# big7segment.net
KiCad netlist of a schematic drawn in EAGLE
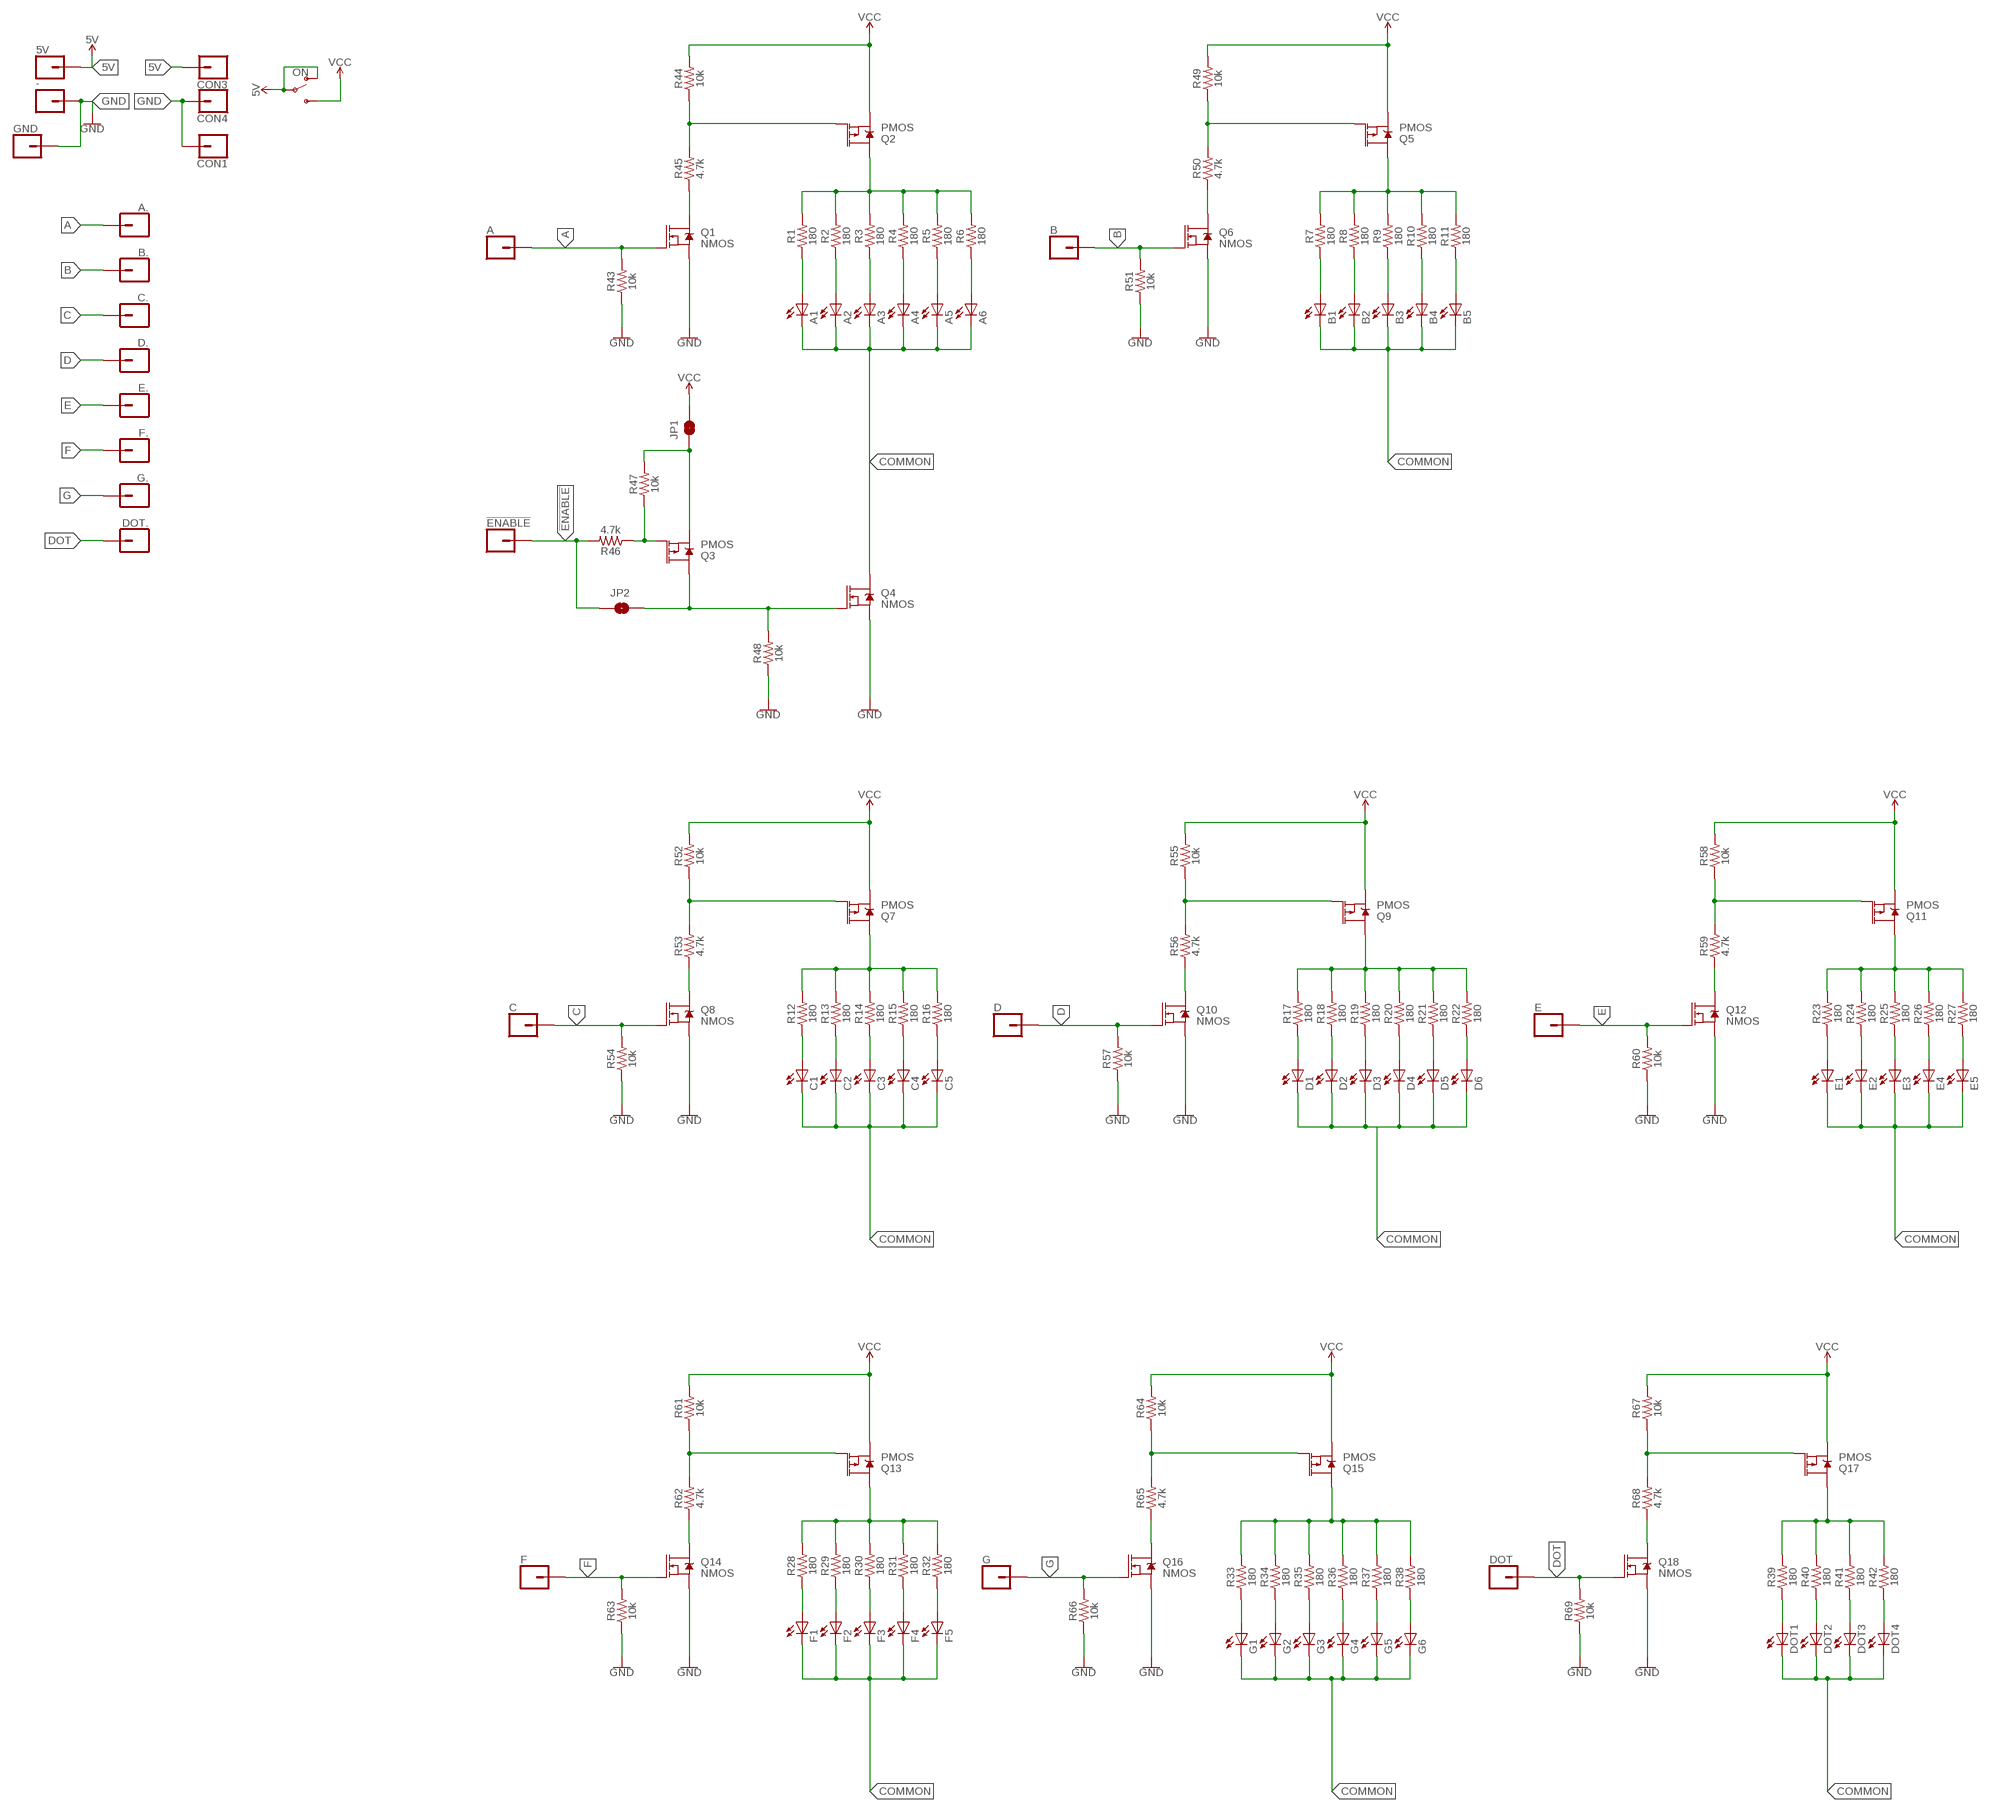
[diagram p0: schematic, sheet 1]

(export (version "E")
  (design (tool "Eeschema 10.0.6"))
  (components
    (comp (ref "!ENABLE!")
      (value "CONN_01OFFSET")
      (footprint "eagle-import:1X01_OFFSET")
      (libsource (lib "eagle-import") (part "CONN_01OFFSET"))
    )
    (comp (ref "-")
      (value "CONN_01OFFSET")
      (footprint "eagle-import:1X01_OFFSET")
      (libsource (lib "eagle-import") (part "CONN_01OFFSET"))
    )
    (comp (ref "5V")
      (value "CONN_01OFFSET")
      (footprint "eagle-import:1X01_OFFSET")
      (libsource (lib "eagle-import") (part "CONN_01OFFSET"))
    )
    (comp (ref "A")
      (value "CONN_01OFFSET")
      (footprint "eagle-import:1X01_OFFSET")
      (libsource (lib "eagle-import") (part "CONN_01OFFSET"))
    )
    (comp (ref "A.")
      (value "CONN_01OFFSET")
      (footprint "eagle-import:1X01_OFFSET")
      (libsource (lib "eagle-import") (part "CONN_01OFFSET"))
    )
    (comp (ref "A1")
      (value "LEDSML0805")
      (footprint "eagle-import:SML0805")
      (libsource (lib "eagle-import") (part "LEDSML0805"))
    )
    (comp (ref "A2")
      (value "LEDSML0805")
      (footprint "eagle-import:SML0805")
      (libsource (lib "eagle-import") (part "LEDSML0805"))
    )
    (comp (ref "A3")
      (value "LEDSML0805")
      (footprint "eagle-import:SML0805")
      (libsource (lib "eagle-import") (part "LEDSML0805"))
    )
    (comp (ref "A4")
      (value "LEDSML0805")
      (footprint "eagle-import:SML0805")
      (libsource (lib "eagle-import") (part "LEDSML0805"))
    )
    (comp (ref "A5")
      (value "LEDSML0805")
      (footprint "eagle-import:SML0805")
      (libsource (lib "eagle-import") (part "LEDSML0805"))
    )
    (comp (ref "A6")
      (value "LEDSML0805")
      (footprint "eagle-import:SML0805")
      (libsource (lib "eagle-import") (part "LEDSML0805"))
    )
    (comp (ref "B")
      (value "CONN_01OFFSET")
      (footprint "eagle-import:1X01_OFFSET")
      (libsource (lib "eagle-import") (part "CONN_01OFFSET"))
    )
    (comp (ref "B.")
      (value "CONN_01OFFSET")
      (footprint "eagle-import:1X01_OFFSET")
      (libsource (lib "eagle-import") (part "CONN_01OFFSET"))
    )
    (comp (ref "B1")
      (value "LEDSML0805")
      (footprint "eagle-import:SML0805")
      (libsource (lib "eagle-import") (part "LEDSML0805"))
    )
    (comp (ref "B2")
      (value "LEDSML0805")
      (footprint "eagle-import:SML0805")
      (libsource (lib "eagle-import") (part "LEDSML0805"))
    )
    (comp (ref "B3")
      (value "LEDSML0805")
      (footprint "eagle-import:SML0805")
      (libsource (lib "eagle-import") (part "LEDSML0805"))
    )
    (comp (ref "B4")
      (value "LEDSML0805")
      (footprint "eagle-import:SML0805")
      (libsource (lib "eagle-import") (part "LEDSML0805"))
    )
    (comp (ref "B5")
      (value "LEDSML0805")
      (footprint "eagle-import:SML0805")
      (libsource (lib "eagle-import") (part "LEDSML0805"))
    )
    (comp (ref "C")
      (value "CONN_01OFFSET")
      (footprint "eagle-import:1X01_OFFSET")
      (libsource (lib "eagle-import") (part "CONN_01OFFSET"))
    )
    (comp (ref "C.")
      (value "CONN_01OFFSET")
      (footprint "eagle-import:1X01_OFFSET")
      (libsource (lib "eagle-import") (part "CONN_01OFFSET"))
    )
    (comp (ref "C1")
      (value "LEDSML0805")
      (footprint "eagle-import:SML0805")
      (libsource (lib "eagle-import") (part "LEDSML0805"))
    )
    (comp (ref "C2")
      (value "LEDSML0805")
      (footprint "eagle-import:SML0805")
      (libsource (lib "eagle-import") (part "LEDSML0805"))
    )
    (comp (ref "C3")
      (value "LEDSML0805")
      (footprint "eagle-import:SML0805")
      (libsource (lib "eagle-import") (part "LEDSML0805"))
    )
    (comp (ref "C4")
      (value "LEDSML0805")
      (footprint "eagle-import:SML0805")
      (libsource (lib "eagle-import") (part "LEDSML0805"))
    )
    (comp (ref "C5")
      (value "LEDSML0805")
      (footprint "eagle-import:SML0805")
      (libsource (lib "eagle-import") (part "LEDSML0805"))
    )
    (comp (ref "CON1")
      (value "CONN_01OFFSET")
      (footprint "eagle-import:1X01_OFFSET")
      (libsource (lib "eagle-import") (part "CONN_01OFFSET"))
    )
    (comp (ref "CON3")
      (value "CONN_01OFFSET")
      (footprint "eagle-import:1X01_OFFSET")
      (libsource (lib "eagle-import") (part "CONN_01OFFSET"))
    )
    (comp (ref "CON4")
      (value "CONN_01OFFSET")
      (footprint "eagle-import:1X01_OFFSET")
      (libsource (lib "eagle-import") (part "CONN_01OFFSET"))
    )
    (comp (ref "D")
      (value "CONN_01OFFSET")
      (footprint "eagle-import:1X01_OFFSET")
      (libsource (lib "eagle-import") (part "CONN_01OFFSET"))
    )
    (comp (ref "D.")
      (value "CONN_01OFFSET")
      (footprint "eagle-import:1X01_OFFSET")
      (libsource (lib "eagle-import") (part "CONN_01OFFSET"))
    )
    (comp (ref "D1")
      (value "LEDSML0805")
      (footprint "eagle-import:SML0805")
      (libsource (lib "eagle-import") (part "LEDSML0805"))
    )
    (comp (ref "D2")
      (value "LEDSML0805")
      (footprint "eagle-import:SML0805")
      (libsource (lib "eagle-import") (part "LEDSML0805"))
    )
    (comp (ref "D3")
      (value "LEDSML0805")
      (footprint "eagle-import:SML0805")
      (libsource (lib "eagle-import") (part "LEDSML0805"))
    )
    (comp (ref "D4")
      (value "LEDSML0805")
      (footprint "eagle-import:SML0805")
      (libsource (lib "eagle-import") (part "LEDSML0805"))
    )
    (comp (ref "D5")
      (value "LEDSML0805")
      (footprint "eagle-import:SML0805")
      (libsource (lib "eagle-import") (part "LEDSML0805"))
    )
    (comp (ref "D6")
      (value "LEDSML0805")
      (footprint "eagle-import:SML0805")
      (libsource (lib "eagle-import") (part "LEDSML0805"))
    )
    (comp (ref "DOT")
      (value "CONN_01OFFSET")
      (footprint "eagle-import:1X01_OFFSET")
      (libsource (lib "eagle-import") (part "CONN_01OFFSET"))
    )
    (comp (ref "DOT.")
      (value "CONN_01OFFSET")
      (footprint "eagle-import:1X01_OFFSET")
      (libsource (lib "eagle-import") (part "CONN_01OFFSET"))
    )
    (comp (ref "DOT1")
      (value "LEDSML0805")
      (footprint "eagle-import:SML0805")
      (libsource (lib "eagle-import") (part "LEDSML0805"))
    )
    (comp (ref "DOT2")
      (value "LEDSML0805")
      (footprint "eagle-import:SML0805")
      (libsource (lib "eagle-import") (part "LEDSML0805"))
    )
    (comp (ref "DOT3")
      (value "LEDSML0805")
      (footprint "eagle-import:SML0805")
      (libsource (lib "eagle-import") (part "LEDSML0805"))
    )
    (comp (ref "DOT4")
      (value "LEDSML0805")
      (footprint "eagle-import:SML0805")
      (libsource (lib "eagle-import") (part "LEDSML0805"))
    )
    (comp (ref "E")
      (value "CONN_01OFFSET")
      (footprint "eagle-import:1X01_OFFSET")
      (libsource (lib "eagle-import") (part "CONN_01OFFSET"))
    )
    (comp (ref "E.")
      (value "CONN_01OFFSET")
      (footprint "eagle-import:1X01_OFFSET")
      (libsource (lib "eagle-import") (part "CONN_01OFFSET"))
    )
    (comp (ref "E1")
      (value "LEDSML0805")
      (footprint "eagle-import:SML0805")
      (libsource (lib "eagle-import") (part "LEDSML0805"))
    )
    (comp (ref "E2")
      (value "LEDSML0805")
      (footprint "eagle-import:SML0805")
      (libsource (lib "eagle-import") (part "LEDSML0805"))
    )
    (comp (ref "E3")
      (value "LEDSML0805")
      (footprint "eagle-import:SML0805")
      (libsource (lib "eagle-import") (part "LEDSML0805"))
    )
    (comp (ref "E4")
      (value "LEDSML0805")
      (footprint "eagle-import:SML0805")
      (libsource (lib "eagle-import") (part "LEDSML0805"))
    )
    (comp (ref "E5")
      (value "LEDSML0805")
      (footprint "eagle-import:SML0805")
      (libsource (lib "eagle-import") (part "LEDSML0805"))
    )
    (comp (ref "F")
      (value "CONN_01OFFSET")
      (footprint "eagle-import:1X01_OFFSET")
      (libsource (lib "eagle-import") (part "CONN_01OFFSET"))
    )
    (comp (ref "F.")
      (value "CONN_01OFFSET")
      (footprint "eagle-import:1X01_OFFSET")
      (libsource (lib "eagle-import") (part "CONN_01OFFSET"))
    )
    (comp (ref "F1")
      (value "LEDSML0805")
      (footprint "eagle-import:SML0805")
      (libsource (lib "eagle-import") (part "LEDSML0805"))
    )
    (comp (ref "F2")
      (value "LEDSML0805")
      (footprint "eagle-import:SML0805")
      (libsource (lib "eagle-import") (part "LEDSML0805"))
    )
    (comp (ref "F3")
      (value "LEDSML0805")
      (footprint "eagle-import:SML0805")
      (libsource (lib "eagle-import") (part "LEDSML0805"))
    )
    (comp (ref "F4")
      (value "LEDSML0805")
      (footprint "eagle-import:SML0805")
      (libsource (lib "eagle-import") (part "LEDSML0805"))
    )
    (comp (ref "F5")
      (value "LEDSML0805")
      (footprint "eagle-import:SML0805")
      (libsource (lib "eagle-import") (part "LEDSML0805"))
    )
    (comp (ref "G")
      (value "CONN_01OFFSET")
      (footprint "eagle-import:1X01_OFFSET")
      (libsource (lib "eagle-import") (part "CONN_01OFFSET"))
    )
    (comp (ref "G.")
      (value "CONN_01OFFSET")
      (footprint "eagle-import:1X01_OFFSET")
      (libsource (lib "eagle-import") (part "CONN_01OFFSET"))
    )
    (comp (ref "G1")
      (value "LEDSML0805")
      (footprint "eagle-import:SML0805")
      (libsource (lib "eagle-import") (part "LEDSML0805"))
    )
    (comp (ref "G2")
      (value "LEDSML0805")
      (footprint "eagle-import:SML0805")
      (libsource (lib "eagle-import") (part "LEDSML0805"))
    )
    (comp (ref "G3")
      (value "LEDSML0805")
      (footprint "eagle-import:SML0805")
      (libsource (lib "eagle-import") (part "LEDSML0805"))
    )
    (comp (ref "G4")
      (value "LEDSML0805")
      (footprint "eagle-import:SML0805")
      (libsource (lib "eagle-import") (part "LEDSML0805"))
    )
    (comp (ref "G5")
      (value "LEDSML0805")
      (footprint "eagle-import:SML0805")
      (libsource (lib "eagle-import") (part "LEDSML0805"))
    )
    (comp (ref "G6")
      (value "LEDSML0805")
      (footprint "eagle-import:SML0805")
      (libsource (lib "eagle-import") (part "LEDSML0805"))
    )
    (comp (ref "GND")
      (value "CONN_01OFFSET")
      (footprint "eagle-import:1X01_OFFSET")
      (libsource (lib "eagle-import") (part "CONN_01OFFSET"))
    )
    (comp (ref "JP1")
      (value "JUMPER-SMT_2_NC_TRACE_NO-SILK")
      (footprint "eagle-import:SMT-JUMPER_2_NC_TRACE_NO-SILK")
      (libsource (lib "eagle-import") (part "JUMPER-SMT_2_NC_TRACE_NO-SILK"))
    )
    (comp (ref "JP2")
      (value "JUMPER-SMT_2_NO_NO-SILK")
      (footprint "eagle-import:SMT-JUMPER_2_NO_NO-SILK")
      (libsource (lib "eagle-import") (part "JUMPER-SMT_2_NO_NO-SILK"))
    )
    (comp (ref "ON")
      (value "SWITCH-SPDT-PTH-11.6X4.0MM")
      (footprint "eagle-import:SWITCH_SPDT_PTH_11.6X4.0MM")
      (libsource (lib "eagle-import") (part "SWITCH-SPDT-PTH-11.6X4.0MM"))
    )
    (comp (ref "Q1")
      (value "NMOS")
      (footprint "eagle-import:SOT23-3")
      (libsource (lib "eagle-import") (part "MOSFET-NCH-AO3404A"))
    )
    (comp (ref "Q2")
      (value "PMOS")
      (footprint "eagle-import:SOT23-3")
      (libsource (lib "eagle-import") (part "MOSFET_PCH-DMG2307L"))
    )
    (comp (ref "Q3")
      (value "PMOS")
      (footprint "eagle-import:SOT23-3")
      (libsource (lib "eagle-import") (part "MOSFET_PCH-DMG2307L"))
    )
    (comp (ref "Q4")
      (value "NMOS")
      (footprint "eagle-import:SOT23-3")
      (libsource (lib "eagle-import") (part "MOSFET-NCH-AO3404A"))
    )
    (comp (ref "Q5")
      (value "PMOS")
      (footprint "eagle-import:SOT23-3")
      (libsource (lib "eagle-import") (part "MOSFET_PCH-DMG2307L"))
    )
    (comp (ref "Q6")
      (value "NMOS")
      (footprint "eagle-import:SOT23-3")
      (libsource (lib "eagle-import") (part "MOSFET-NCH-AO3404A"))
    )
    (comp (ref "Q7")
      (value "PMOS")
      (footprint "eagle-import:SOT23-3")
      (libsource (lib "eagle-import") (part "MOSFET_PCH-DMG2307L"))
    )
    (comp (ref "Q8")
      (value "NMOS")
      (footprint "eagle-import:SOT23-3")
      (libsource (lib "eagle-import") (part "MOSFET-NCH-AO3404A"))
    )
    (comp (ref "Q9")
      (value "PMOS")
      (footprint "eagle-import:SOT23-3")
      (libsource (lib "eagle-import") (part "MOSFET_PCH-DMG2307L"))
    )
    (comp (ref "Q10")
      (value "NMOS")
      (footprint "eagle-import:SOT23-3")
      (libsource (lib "eagle-import") (part "MOSFET-NCH-AO3404A"))
    )
    (comp (ref "Q11")
      (value "PMOS")
      (footprint "eagle-import:SOT23-3")
      (libsource (lib "eagle-import") (part "MOSFET_PCH-DMG2307L"))
    )
    (comp (ref "Q12")
      (value "NMOS")
      (footprint "eagle-import:SOT23-3")
      (libsource (lib "eagle-import") (part "MOSFET-NCH-AO3404A"))
    )
    (comp (ref "Q13")
      (value "PMOS")
      (footprint "eagle-import:SOT23-3")
      (libsource (lib "eagle-import") (part "MOSFET_PCH-DMG2307L"))
    )
    (comp (ref "Q14")
      (value "NMOS")
      (footprint "eagle-import:SOT23-3")
      (libsource (lib "eagle-import") (part "MOSFET-NCH-AO3404A"))
    )
    (comp (ref "Q15")
      (value "PMOS")
      (footprint "eagle-import:SOT23-3")
      (libsource (lib "eagle-import") (part "MOSFET_PCH-DMG2307L"))
    )
    (comp (ref "Q16")
      (value "NMOS")
      (footprint "eagle-import:SOT23-3")
      (libsource (lib "eagle-import") (part "MOSFET-NCH-AO3404A"))
    )
    (comp (ref "Q17")
      (value "PMOS")
      (footprint "eagle-import:SOT23-3")
      (libsource (lib "eagle-import") (part "MOSFET_PCH-DMG2307L"))
    )
    (comp (ref "Q18")
      (value "NMOS")
      (footprint "eagle-import:SOT23-3")
      (libsource (lib "eagle-import") (part "MOSFET-NCH-AO3404A"))
    )
    (comp (ref "R1")
      (value "180")
      (footprint "eagle-import:0805")
      (libsource (lib "eagle-import") (part "0.3OHM-0805-1/8W-1%"))
    )
    (comp (ref "R2")
      (value "180")
      (footprint "eagle-import:0805")
      (libsource (lib "eagle-import") (part "0.3OHM-0805-1/8W-1%"))
    )
    (comp (ref "R3")
      (value "180")
      (footprint "eagle-import:0805")
      (libsource (lib "eagle-import") (part "0.3OHM-0805-1/8W-1%"))
    )
    (comp (ref "R4")
      (value "180")
      (footprint "eagle-import:0805")
      (libsource (lib "eagle-import") (part "0.3OHM-0805-1/8W-1%"))
    )
    (comp (ref "R5")
      (value "180")
      (footprint "eagle-import:0805")
      (libsource (lib "eagle-import") (part "0.3OHM-0805-1/8W-1%"))
    )
    (comp (ref "R6")
      (value "180")
      (footprint "eagle-import:0805")
      (libsource (lib "eagle-import") (part "0.3OHM-0805-1/8W-1%"))
    )
    (comp (ref "R7")
      (value "180")
      (footprint "eagle-import:0805")
      (libsource (lib "eagle-import") (part "0.3OHM-0805-1/8W-1%"))
    )
    (comp (ref "R8")
      (value "180")
      (footprint "eagle-import:0805")
      (libsource (lib "eagle-import") (part "0.3OHM-0805-1/8W-1%"))
    )
    (comp (ref "R9")
      (value "180")
      (footprint "eagle-import:0805")
      (libsource (lib "eagle-import") (part "0.3OHM-0805-1/8W-1%"))
    )
    (comp (ref "R10")
      (value "180")
      (footprint "eagle-import:0805")
      (libsource (lib "eagle-import") (part "0.3OHM-0805-1/8W-1%"))
    )
    (comp (ref "R11")
      (value "180")
      (footprint "eagle-import:0805")
      (libsource (lib "eagle-import") (part "0.3OHM-0805-1/8W-1%"))
    )
    (comp (ref "R12")
      (value "180")
      (footprint "eagle-import:0805")
      (libsource (lib "eagle-import") (part "0.3OHM-0805-1/8W-1%"))
    )
    (comp (ref "R13")
      (value "180")
      (footprint "eagle-import:0805")
      (libsource (lib "eagle-import") (part "0.3OHM-0805-1/8W-1%"))
    )
    (comp (ref "R14")
      (value "180")
      (footprint "eagle-import:0805")
      (libsource (lib "eagle-import") (part "0.3OHM-0805-1/8W-1%"))
    )
    (comp (ref "R15")
      (value "180")
      (footprint "eagle-import:0805")
      (libsource (lib "eagle-import") (part "0.3OHM-0805-1/8W-1%"))
    )
    (comp (ref "R16")
      (value "180")
      (footprint "eagle-import:0805")
      (libsource (lib "eagle-import") (part "0.3OHM-0805-1/8W-1%"))
    )
    (comp (ref "R17")
      (value "180")
      (footprint "eagle-import:0805")
      (libsource (lib "eagle-import") (part "0.3OHM-0805-1/8W-1%"))
    )
    (comp (ref "R18")
      (value "180")
      (footprint "eagle-import:0805")
      (libsource (lib "eagle-import") (part "0.3OHM-0805-1/8W-1%"))
    )
    (comp (ref "R19")
      (value "180")
      (footprint "eagle-import:0805")
      (libsource (lib "eagle-import") (part "0.3OHM-0805-1/8W-1%"))
    )
    (comp (ref "R20")
      (value "180")
      (footprint "eagle-import:0805")
      (libsource (lib "eagle-import") (part "0.3OHM-0805-1/8W-1%"))
    )
    (comp (ref "R21")
      (value "180")
      (footprint "eagle-import:0805")
      (libsource (lib "eagle-import") (part "0.3OHM-0805-1/8W-1%"))
    )
    (comp (ref "R22")
      (value "180")
      (footprint "eagle-import:0805")
      (libsource (lib "eagle-import") (part "0.3OHM-0805-1/8W-1%"))
    )
    (comp (ref "R23")
      (value "180")
      (footprint "eagle-import:0805")
      (libsource (lib "eagle-import") (part "0.3OHM-0805-1/8W-1%"))
    )
    (comp (ref "R24")
      (value "180")
      (footprint "eagle-import:0805")
      (libsource (lib "eagle-import") (part "0.3OHM-0805-1/8W-1%"))
    )
    (comp (ref "R25")
      (value "180")
      (footprint "eagle-import:0805")
      (libsource (lib "eagle-import") (part "0.3OHM-0805-1/8W-1%"))
    )
    (comp (ref "R26")
      (value "180")
      (footprint "eagle-import:0805")
      (libsource (lib "eagle-import") (part "0.3OHM-0805-1/8W-1%"))
    )
    (comp (ref "R27")
      (value "180")
      (footprint "eagle-import:0805")
      (libsource (lib "eagle-import") (part "0.3OHM-0805-1/8W-1%"))
    )
    (comp (ref "R28")
      (value "180")
      (footprint "eagle-import:0805")
      (libsource (lib "eagle-import") (part "0.3OHM-0805-1/8W-1%"))
    )
    (comp (ref "R29")
      (value "180")
      (footprint "eagle-import:0805")
      (libsource (lib "eagle-import") (part "0.3OHM-0805-1/8W-1%"))
    )
    (comp (ref "R30")
      (value "180")
      (footprint "eagle-import:0805")
      (libsource (lib "eagle-import") (part "0.3OHM-0805-1/8W-1%"))
    )
    (comp (ref "R31")
      (value "180")
      (footprint "eagle-import:0805")
      (libsource (lib "eagle-import") (part "0.3OHM-0805-1/8W-1%"))
    )
    (comp (ref "R32")
      (value "180")
      (footprint "eagle-import:0805")
      (libsource (lib "eagle-import") (part "0.3OHM-0805-1/8W-1%"))
    )
    (comp (ref "R33")
      (value "180")
      (footprint "eagle-import:0805")
      (libsource (lib "eagle-import") (part "0.3OHM-0805-1/8W-1%"))
    )
    (comp (ref "R34")
      (value "180")
      (footprint "eagle-import:0805")
      (libsource (lib "eagle-import") (part "0.3OHM-0805-1/8W-1%"))
    )
    (comp (ref "R35")
      (value "180")
      (footprint "eagle-import:0805")
      (libsource (lib "eagle-import") (part "0.3OHM-0805-1/8W-1%"))
    )
    (comp (ref "R36")
      (value "180")
      (footprint "eagle-import:0805")
      (libsource (lib "eagle-import") (part "0.3OHM-0805-1/8W-1%"))
    )
    (comp (ref "R37")
      (value "180")
      (footprint "eagle-import:0805")
      (libsource (lib "eagle-import") (part "0.3OHM-0805-1/8W-1%"))
    )
    (comp (ref "R38")
      (value "180")
      (footprint "eagle-import:0805")
      (libsource (lib "eagle-import") (part "0.3OHM-0805-1/8W-1%"))
    )
    (comp (ref "R39")
      (value "180")
      (footprint "eagle-import:0805")
      (libsource (lib "eagle-import") (part "0.3OHM-0805-1/8W-1%"))
    )
    (comp (ref "R40")
      (value "180")
      (footprint "eagle-import:0805")
      (libsource (lib "eagle-import") (part "0.3OHM-0805-1/8W-1%"))
    )
    (comp (ref "R41")
      (value "180")
      (footprint "eagle-import:0805")
      (libsource (lib "eagle-import") (part "0.3OHM-0805-1/8W-1%"))
    )
    (comp (ref "R42")
      (value "180")
      (footprint "eagle-import:0805")
      (libsource (lib "eagle-import") (part "0.3OHM-0805-1/8W-1%"))
    )
    (comp (ref "R43")
      (value "10k")
      (footprint "eagle-import:0805")
      (libsource (lib "eagle-import") (part "0.3OHM-0805-1/8W-1%"))
    )
    (comp (ref "R44")
      (value "10k")
      (footprint "eagle-import:0805")
      (libsource (lib "eagle-import") (part "0.3OHM-0805-1/8W-1%"))
    )
    (comp (ref "R45")
      (value "4.7k")
      (footprint "eagle-import:0805")
      (libsource (lib "eagle-import") (part "0.3OHM-0805-1/8W-1%"))
    )
    (comp (ref "R46")
      (value "4.7k")
      (footprint "eagle-import:0805")
      (libsource (lib "eagle-import") (part "0.3OHM-0805-1/8W-1%"))
    )
    (comp (ref "R47")
      (value "10k")
      (footprint "eagle-import:0805")
      (libsource (lib "eagle-import") (part "0.3OHM-0805-1/8W-1%"))
    )
    (comp (ref "R48")
      (value "10k")
      (footprint "eagle-import:0805")
      (libsource (lib "eagle-import") (part "0.3OHM-0805-1/8W-1%"))
    )
    (comp (ref "R49")
      (value "10k")
      (footprint "eagle-import:0805")
      (libsource (lib "eagle-import") (part "0.3OHM-0805-1/8W-1%"))
    )
    (comp (ref "R50")
      (value "4.7k")
      (footprint "eagle-import:0805")
      (libsource (lib "eagle-import") (part "0.3OHM-0805-1/8W-1%"))
    )
    (comp (ref "R51")
      (value "10k")
      (footprint "eagle-import:0805")
      (libsource (lib "eagle-import") (part "0.3OHM-0805-1/8W-1%"))
    )
    (comp (ref "R52")
      (value "10k")
      (footprint "eagle-import:0805")
      (libsource (lib "eagle-import") (part "0.3OHM-0805-1/8W-1%"))
    )
    (comp (ref "R53")
      (value "4.7k")
      (footprint "eagle-import:0805")
      (libsource (lib "eagle-import") (part "0.3OHM-0805-1/8W-1%"))
    )
    (comp (ref "R54")
      (value "10k")
      (footprint "eagle-import:0805")
      (libsource (lib "eagle-import") (part "0.3OHM-0805-1/8W-1%"))
    )
    (comp (ref "R55")
      (value "10k")
      (footprint "eagle-import:0805")
      (libsource (lib "eagle-import") (part "0.3OHM-0805-1/8W-1%"))
    )
    (comp (ref "R56")
      (value "4.7k")
      (footprint "eagle-import:0805")
      (libsource (lib "eagle-import") (part "0.3OHM-0805-1/8W-1%"))
    )
    (comp (ref "R57")
      (value "10k")
      (footprint "eagle-import:0805")
      (libsource (lib "eagle-import") (part "0.3OHM-0805-1/8W-1%"))
    )
    (comp (ref "R58")
      (value "10k")
      (footprint "eagle-import:0805")
      (libsource (lib "eagle-import") (part "0.3OHM-0805-1/8W-1%"))
    )
    (comp (ref "R59")
      (value "4.7k")
      (footprint "eagle-import:0805")
      (libsource (lib "eagle-import") (part "0.3OHM-0805-1/8W-1%"))
    )
    (comp (ref "R60")
      (value "10k")
      (footprint "eagle-import:0805")
      (libsource (lib "eagle-import") (part "0.3OHM-0805-1/8W-1%"))
    )
    (comp (ref "R61")
      (value "10k")
      (footprint "eagle-import:0805")
      (libsource (lib "eagle-import") (part "0.3OHM-0805-1/8W-1%"))
    )
    (comp (ref "R62")
      (value "4.7k")
      (footprint "eagle-import:0805")
      (libsource (lib "eagle-import") (part "0.3OHM-0805-1/8W-1%"))
    )
    (comp (ref "R63")
      (value "10k")
      (footprint "eagle-import:0805")
      (libsource (lib "eagle-import") (part "0.3OHM-0805-1/8W-1%"))
    )
    (comp (ref "R64")
      (value "10k")
      (footprint "eagle-import:0805")
      (libsource (lib "eagle-import") (part "0.3OHM-0805-1/8W-1%"))
    )
    (comp (ref "R65")
      (value "4.7k")
      (footprint "eagle-import:0805")
      (libsource (lib "eagle-import") (part "0.3OHM-0805-1/8W-1%"))
    )
    (comp (ref "R66")
      (value "10k")
      (footprint "eagle-import:0805")
      (libsource (lib "eagle-import") (part "0.3OHM-0805-1/8W-1%"))
    )
    (comp (ref "R67")
      (value "10k")
      (footprint "eagle-import:0805")
      (libsource (lib "eagle-import") (part "0.3OHM-0805-1/8W-1%"))
    )
    (comp (ref "R68")
      (value "4.7k")
      (footprint "eagle-import:0805")
      (libsource (lib "eagle-import") (part "0.3OHM-0805-1/8W-1%"))
    )
    (comp (ref "R69")
      (value "10k")
      (footprint "eagle-import:0805")
      (libsource (lib "eagle-import") (part "0.3OHM-0805-1/8W-1%"))
    )
  )
  (nets
    (net (code "1") (name "/~{ENABLE}") (class "Default")
      (node (ref "!ENABLE!") (pin "1") (pinfunction "1_1") (pintype "passive"))
      (node (ref "JP2") (pin "1") (pinfunction "1_1") (pintype "passive"))
      (node (ref "R46") (pin "2") (pinfunction "2_2") (pintype "passive"))
    )
    (net (code "2") (name "5V") (class "Default")
      (node (ref "5V") (pin "1") (pinfunction "1_1") (pintype "passive"))
      (node (ref "CON3") (pin "1") (pinfunction "1_1") (pintype "passive"))
      (node (ref "ON") (pin "1") (pinfunction "O_1") (pintype "passive"))
      (node (ref "ON") (pin "2") (pinfunction "P_2") (pintype "passive"))
    )
    (net (code "3") (name "A") (class "Default")
      (node (ref "A") (pin "1") (pinfunction "1_1") (pintype "passive"))
      (node (ref "A.") (pin "1") (pinfunction "1_1") (pintype "passive"))
      (node (ref "Q1") (pin "1") (pinfunction "G_1") (pintype "bidirectional"))
      (node (ref "R43") (pin "2") (pinfunction "2_2") (pintype "passive"))
    )
    (net (code "4") (name "B") (class "Default")
      (node (ref "B") (pin "1") (pinfunction "1_1") (pintype "passive"))
      (node (ref "B.") (pin "1") (pinfunction "1_1") (pintype "passive"))
      (node (ref "Q6") (pin "1") (pinfunction "G_1") (pintype "bidirectional"))
      (node (ref "R51") (pin "2") (pinfunction "2_2") (pintype "passive"))
    )
    (net (code "5") (name "C") (class "Default")
      (node (ref "C") (pin "1") (pinfunction "1_1") (pintype "passive"))
      (node (ref "C.") (pin "1") (pinfunction "1_1") (pintype "passive"))
      (node (ref "Q8") (pin "1") (pinfunction "G_1") (pintype "bidirectional"))
      (node (ref "R54") (pin "2") (pinfunction "2_2") (pintype "passive"))
    )
    (net (code "6") (name "COMMON") (class "Default")
      (node (ref "A1") (pin "C") (pinfunction "C_C") (pintype "passive"))
      (node (ref "A2") (pin "C") (pinfunction "C_C") (pintype "passive"))
      (node (ref "A3") (pin "C") (pinfunction "C_C") (pintype "passive"))
      (node (ref "A4") (pin "C") (pinfunction "C_C") (pintype "passive"))
      (node (ref "A5") (pin "C") (pinfunction "C_C") (pintype "passive"))
      (node (ref "A6") (pin "C") (pinfunction "C_C") (pintype "passive"))
      (node (ref "B1") (pin "C") (pinfunction "C_C") (pintype "passive"))
      (node (ref "B2") (pin "C") (pinfunction "C_C") (pintype "passive"))
      (node (ref "B3") (pin "C") (pinfunction "C_C") (pintype "passive"))
      (node (ref "B4") (pin "C") (pinfunction "C_C") (pintype "passive"))
      (node (ref "B5") (pin "C") (pinfunction "C_C") (pintype "passive"))
      (node (ref "C1") (pin "C") (pinfunction "C_C") (pintype "passive"))
      (node (ref "C2") (pin "C") (pinfunction "C_C") (pintype "passive"))
      (node (ref "C3") (pin "C") (pinfunction "C_C") (pintype "passive"))
      (node (ref "C4") (pin "C") (pinfunction "C_C") (pintype "passive"))
      (node (ref "C5") (pin "C") (pinfunction "C_C") (pintype "passive"))
      (node (ref "D1") (pin "C") (pinfunction "C_C") (pintype "passive"))
      (node (ref "D2") (pin "C") (pinfunction "C_C") (pintype "passive"))
      (node (ref "D3") (pin "C") (pinfunction "C_C") (pintype "passive"))
      (node (ref "D4") (pin "C") (pinfunction "C_C") (pintype "passive"))
      (node (ref "D5") (pin "C") (pinfunction "C_C") (pintype "passive"))
      (node (ref "D6") (pin "C") (pinfunction "C_C") (pintype "passive"))
      (node (ref "DOT1") (pin "C") (pinfunction "C_C") (pintype "passive"))
      (node (ref "DOT2") (pin "C") (pinfunction "C_C") (pintype "passive"))
      (node (ref "DOT3") (pin "C") (pinfunction "C_C") (pintype "passive"))
      (node (ref "DOT4") (pin "C") (pinfunction "C_C") (pintype "passive"))
      (node (ref "E1") (pin "C") (pinfunction "C_C") (pintype "passive"))
      (node (ref "E2") (pin "C") (pinfunction "C_C") (pintype "passive"))
      (node (ref "E3") (pin "C") (pinfunction "C_C") (pintype "passive"))
      (node (ref "E4") (pin "C") (pinfunction "C_C") (pintype "passive"))
      (node (ref "E5") (pin "C") (pinfunction "C_C") (pintype "passive"))
      (node (ref "F1") (pin "C") (pinfunction "C_C") (pintype "passive"))
      (node (ref "F2") (pin "C") (pinfunction "C_C") (pintype "passive"))
      (node (ref "F3") (pin "C") (pinfunction "C_C") (pintype "passive"))
      (node (ref "F4") (pin "C") (pinfunction "C_C") (pintype "passive"))
      (node (ref "F5") (pin "C") (pinfunction "C_C") (pintype "passive"))
      (node (ref "G1") (pin "C") (pinfunction "C_C") (pintype "passive"))
      (node (ref "G2") (pin "C") (pinfunction "C_C") (pintype "passive"))
      (node (ref "G3") (pin "C") (pinfunction "C_C") (pintype "passive"))
      (node (ref "G4") (pin "C") (pinfunction "C_C") (pintype "passive"))
      (node (ref "G5") (pin "C") (pinfunction "C_C") (pintype "passive"))
      (node (ref "G6") (pin "C") (pinfunction "C_C") (pintype "passive"))
      (node (ref "Q4") (pin "3") (pinfunction "D_3") (pintype "bidirectional"))
    )
    (net (code "7") (name "D") (class "Default")
      (node (ref "D") (pin "1") (pinfunction "1_1") (pintype "passive"))
      (node (ref "D.") (pin "1") (pinfunction "1_1") (pintype "passive"))
      (node (ref "Q10") (pin "1") (pinfunction "G_1") (pintype "bidirectional"))
      (node (ref "R57") (pin "2") (pinfunction "2_2") (pintype "passive"))
    )
    (net (code "8") (name "DOT") (class "Default")
      (node (ref "DOT") (pin "1") (pinfunction "1_1") (pintype "passive"))
      (node (ref "DOT.") (pin "1") (pinfunction "1_1") (pintype "passive"))
      (node (ref "Q18") (pin "1") (pinfunction "G_1") (pintype "bidirectional"))
      (node (ref "R69") (pin "2") (pinfunction "2_2") (pintype "passive"))
    )
    (net (code "9") (name "E") (class "Default")
      (node (ref "E") (pin "1") (pinfunction "1_1") (pintype "passive"))
      (node (ref "E.") (pin "1") (pinfunction "1_1") (pintype "passive"))
      (node (ref "Q12") (pin "1") (pinfunction "G_1") (pintype "bidirectional"))
      (node (ref "R60") (pin "2") (pinfunction "2_2") (pintype "passive"))
    )
    (net (code "10") (name "F") (class "Default")
      (node (ref "F") (pin "1") (pinfunction "1_1") (pintype "passive"))
      (node (ref "F.") (pin "1") (pinfunction "1_1") (pintype "passive"))
      (node (ref "Q14") (pin "1") (pinfunction "G_1") (pintype "bidirectional"))
      (node (ref "R63") (pin "2") (pinfunction "2_2") (pintype "passive"))
    )
    (net (code "11") (name "G") (class "Default")
      (node (ref "G") (pin "1") (pinfunction "1_1") (pintype "passive"))
      (node (ref "G.") (pin "1") (pinfunction "1_1") (pintype "passive"))
      (node (ref "Q16") (pin "1") (pinfunction "G_1") (pintype "bidirectional"))
      (node (ref "R66") (pin "2") (pinfunction "2_2") (pintype "passive"))
    )
    (net (code "12") (name "GND") (class "Default")
      (node (ref "-") (pin "1") (pinfunction "1_1") (pintype "passive"))
      (node (ref "CON1") (pin "1") (pinfunction "1_1") (pintype "passive"))
      (node (ref "CON4") (pin "1") (pinfunction "1_1") (pintype "passive"))
      (node (ref "GND") (pin "1") (pinfunction "1_1") (pintype "passive"))
      (node (ref "Q1") (pin "2") (pinfunction "S_2") (pintype "bidirectional"))
      (node (ref "Q10") (pin "2") (pinfunction "S_2") (pintype "bidirectional"))
      (node (ref "Q12") (pin "2") (pinfunction "S_2") (pintype "bidirectional"))
      (node (ref "Q14") (pin "2") (pinfunction "S_2") (pintype "bidirectional"))
      (node (ref "Q16") (pin "2") (pinfunction "S_2") (pintype "bidirectional"))
      (node (ref "Q18") (pin "2") (pinfunction "S_2") (pintype "bidirectional"))
      (node (ref "Q4") (pin "2") (pinfunction "S_2") (pintype "bidirectional"))
      (node (ref "Q6") (pin "2") (pinfunction "S_2") (pintype "bidirectional"))
      (node (ref "Q8") (pin "2") (pinfunction "S_2") (pintype "bidirectional"))
      (node (ref "R43") (pin "1") (pinfunction "1_1") (pintype "passive"))
      (node (ref "R48") (pin "1") (pinfunction "1_1") (pintype "passive"))
      (node (ref "R51") (pin "1") (pinfunction "1_1") (pintype "passive"))
      (node (ref "R54") (pin "1") (pinfunction "1_1") (pintype "passive"))
      (node (ref "R57") (pin "1") (pinfunction "1_1") (pintype "passive"))
      (node (ref "R60") (pin "1") (pinfunction "1_1") (pintype "passive"))
      (node (ref "R63") (pin "1") (pinfunction "1_1") (pintype "passive"))
      (node (ref "R66") (pin "1") (pinfunction "1_1") (pintype "passive"))
      (node (ref "R69") (pin "1") (pinfunction "1_1") (pintype "passive"))
    )
    (net (code "13") (name "Net-(A1-PadA)") (class "Default")
      (node (ref "A1") (pin "A") (pinfunction "A_A") (pintype "passive"))
      (node (ref "R1") (pin "1") (pinfunction "1_1") (pintype "passive"))
    )
    (net (code "14") (name "Net-(A2-PadA)") (class "Default")
      (node (ref "A2") (pin "A") (pinfunction "A_A") (pintype "passive"))
      (node (ref "R2") (pin "1") (pinfunction "1_1") (pintype "passive"))
    )
    (net (code "15") (name "Net-(A3-PadA)") (class "Default")
      (node (ref "A3") (pin "A") (pinfunction "A_A") (pintype "passive"))
      (node (ref "R3") (pin "1") (pinfunction "1_1") (pintype "passive"))
    )
    (net (code "16") (name "Net-(A4-PadA)") (class "Default")
      (node (ref "A4") (pin "A") (pinfunction "A_A") (pintype "passive"))
      (node (ref "R4") (pin "1") (pinfunction "1_1") (pintype "passive"))
    )
    (net (code "17") (name "Net-(A5-PadA)") (class "Default")
      (node (ref "A5") (pin "A") (pinfunction "A_A") (pintype "passive"))
      (node (ref "R5") (pin "1") (pinfunction "1_1") (pintype "passive"))
    )
    (net (code "18") (name "Net-(A6-PadA)") (class "Default")
      (node (ref "A6") (pin "A") (pinfunction "A_A") (pintype "passive"))
      (node (ref "R6") (pin "1") (pinfunction "1_1") (pintype "passive"))
    )
    (net (code "19") (name "Net-(B1-PadA)") (class "Default")
      (node (ref "B1") (pin "A") (pinfunction "A_A") (pintype "passive"))
      (node (ref "R7") (pin "1") (pinfunction "1_1") (pintype "passive"))
    )
    (net (code "20") (name "Net-(B2-PadA)") (class "Default")
      (node (ref "B2") (pin "A") (pinfunction "A_A") (pintype "passive"))
      (node (ref "R8") (pin "1") (pinfunction "1_1") (pintype "passive"))
    )
    (net (code "21") (name "Net-(B3-PadA)") (class "Default")
      (node (ref "B3") (pin "A") (pinfunction "A_A") (pintype "passive"))
      (node (ref "R9") (pin "1") (pinfunction "1_1") (pintype "passive"))
    )
    (net (code "22") (name "Net-(B4-PadA)") (class "Default")
      (node (ref "B4") (pin "A") (pinfunction "A_A") (pintype "passive"))
      (node (ref "R10") (pin "1") (pinfunction "1_1") (pintype "passive"))
    )
    (net (code "23") (name "Net-(B5-PadA)") (class "Default")
      (node (ref "B5") (pin "A") (pinfunction "A_A") (pintype "passive"))
      (node (ref "R11") (pin "1") (pinfunction "1_1") (pintype "passive"))
    )
    (net (code "24") (name "Net-(C1-PadA)") (class "Default")
      (node (ref "C1") (pin "A") (pinfunction "A_A") (pintype "passive"))
      (node (ref "R12") (pin "1") (pinfunction "1_1") (pintype "passive"))
    )
    (net (code "25") (name "Net-(C2-PadA)") (class "Default")
      (node (ref "C2") (pin "A") (pinfunction "A_A") (pintype "passive"))
      (node (ref "R13") (pin "1") (pinfunction "1_1") (pintype "passive"))
    )
    (net (code "26") (name "Net-(C3-PadA)") (class "Default")
      (node (ref "C3") (pin "A") (pinfunction "A_A") (pintype "passive"))
      (node (ref "R14") (pin "1") (pinfunction "1_1") (pintype "passive"))
    )
    (net (code "27") (name "Net-(C4-PadA)") (class "Default")
      (node (ref "C4") (pin "A") (pinfunction "A_A") (pintype "passive"))
      (node (ref "R15") (pin "1") (pinfunction "1_1") (pintype "passive"))
    )
    (net (code "28") (name "Net-(C5-PadA)") (class "Default")
      (node (ref "C5") (pin "A") (pinfunction "A_A") (pintype "passive"))
      (node (ref "R16") (pin "1") (pinfunction "1_1") (pintype "passive"))
    )
    (net (code "29") (name "Net-(D1-PadA)") (class "Default")
      (node (ref "D1") (pin "A") (pinfunction "A_A") (pintype "passive"))
      (node (ref "R17") (pin "1") (pinfunction "1_1") (pintype "passive"))
    )
    (net (code "30") (name "Net-(D2-PadA)") (class "Default")
      (node (ref "D2") (pin "A") (pinfunction "A_A") (pintype "passive"))
      (node (ref "R18") (pin "1") (pinfunction "1_1") (pintype "passive"))
    )
    (net (code "31") (name "Net-(D3-PadA)") (class "Default")
      (node (ref "D3") (pin "A") (pinfunction "A_A") (pintype "passive"))
      (node (ref "R19") (pin "1") (pinfunction "1_1") (pintype "passive"))
    )
    (net (code "32") (name "Net-(D4-PadA)") (class "Default")
      (node (ref "D4") (pin "A") (pinfunction "A_A") (pintype "passive"))
      (node (ref "R20") (pin "1") (pinfunction "1_1") (pintype "passive"))
    )
    (net (code "33") (name "Net-(D5-PadA)") (class "Default")
      (node (ref "D5") (pin "A") (pinfunction "A_A") (pintype "passive"))
      (node (ref "R21") (pin "1") (pinfunction "1_1") (pintype "passive"))
    )
    (net (code "34") (name "Net-(D6-PadA)") (class "Default")
      (node (ref "D6") (pin "A") (pinfunction "A_A") (pintype "passive"))
      (node (ref "R22") (pin "1") (pinfunction "1_1") (pintype "passive"))
    )
    (net (code "35") (name "Net-(DOT1-PadA)") (class "Default")
      (node (ref "DOT1") (pin "A") (pinfunction "A_A") (pintype "passive"))
      (node (ref "R39") (pin "1") (pinfunction "1_1") (pintype "passive"))
    )
    (net (code "36") (name "Net-(DOT2-PadA)") (class "Default")
      (node (ref "DOT2") (pin "A") (pinfunction "A_A") (pintype "passive"))
      (node (ref "R40") (pin "1") (pinfunction "1_1") (pintype "passive"))
    )
    (net (code "37") (name "Net-(DOT3-PadA)") (class "Default")
      (node (ref "DOT3") (pin "A") (pinfunction "A_A") (pintype "passive"))
      (node (ref "R41") (pin "1") (pinfunction "1_1") (pintype "passive"))
    )
    (net (code "38") (name "Net-(DOT4-PadA)") (class "Default")
      (node (ref "DOT4") (pin "A") (pinfunction "A_A") (pintype "passive"))
      (node (ref "R42") (pin "1") (pinfunction "1_1") (pintype "passive"))
    )
    (net (code "39") (name "Net-(E1-PadA)") (class "Default")
      (node (ref "E1") (pin "A") (pinfunction "A_A") (pintype "passive"))
      (node (ref "R23") (pin "1") (pinfunction "1_1") (pintype "passive"))
    )
    (net (code "40") (name "Net-(E2-PadA)") (class "Default")
      (node (ref "E2") (pin "A") (pinfunction "A_A") (pintype "passive"))
      (node (ref "R24") (pin "1") (pinfunction "1_1") (pintype "passive"))
    )
    (net (code "41") (name "Net-(E3-PadA)") (class "Default")
      (node (ref "E3") (pin "A") (pinfunction "A_A") (pintype "passive"))
      (node (ref "R25") (pin "1") (pinfunction "1_1") (pintype "passive"))
    )
    (net (code "42") (name "Net-(E4-PadA)") (class "Default")
      (node (ref "E4") (pin "A") (pinfunction "A_A") (pintype "passive"))
      (node (ref "R26") (pin "1") (pinfunction "1_1") (pintype "passive"))
    )
    (net (code "43") (name "Net-(E5-PadA)") (class "Default")
      (node (ref "E5") (pin "A") (pinfunction "A_A") (pintype "passive"))
      (node (ref "R27") (pin "1") (pinfunction "1_1") (pintype "passive"))
    )
    (net (code "44") (name "Net-(F1-PadA)") (class "Default")
      (node (ref "F1") (pin "A") (pinfunction "A_A") (pintype "passive"))
      (node (ref "R28") (pin "1") (pinfunction "1_1") (pintype "passive"))
    )
    (net (code "45") (name "Net-(F2-PadA)") (class "Default")
      (node (ref "F2") (pin "A") (pinfunction "A_A") (pintype "passive"))
      (node (ref "R29") (pin "1") (pinfunction "1_1") (pintype "passive"))
    )
    (net (code "46") (name "Net-(F3-PadA)") (class "Default")
      (node (ref "F3") (pin "A") (pinfunction "A_A") (pintype "passive"))
      (node (ref "R30") (pin "1") (pinfunction "1_1") (pintype "passive"))
    )
    (net (code "47") (name "Net-(F4-PadA)") (class "Default")
      (node (ref "F4") (pin "A") (pinfunction "A_A") (pintype "passive"))
      (node (ref "R31") (pin "1") (pinfunction "1_1") (pintype "passive"))
    )
    (net (code "48") (name "Net-(F5-PadA)") (class "Default")
      (node (ref "F5") (pin "A") (pinfunction "A_A") (pintype "passive"))
      (node (ref "R32") (pin "1") (pinfunction "1_1") (pintype "passive"))
    )
    (net (code "49") (name "Net-(G1-PadA)") (class "Default")
      (node (ref "G1") (pin "A") (pinfunction "A_A") (pintype "passive"))
      (node (ref "R33") (pin "1") (pinfunction "1_1") (pintype "passive"))
    )
    (net (code "50") (name "Net-(G2-PadA)") (class "Default")
      (node (ref "G2") (pin "A") (pinfunction "A_A") (pintype "passive"))
      (node (ref "R34") (pin "1") (pinfunction "1_1") (pintype "passive"))
    )
    (net (code "51") (name "Net-(G3-PadA)") (class "Default")
      (node (ref "G3") (pin "A") (pinfunction "A_A") (pintype "passive"))
      (node (ref "R35") (pin "1") (pinfunction "1_1") (pintype "passive"))
    )
    (net (code "52") (name "Net-(G4-PadA)") (class "Default")
      (node (ref "G4") (pin "A") (pinfunction "A_A") (pintype "passive"))
      (node (ref "R36") (pin "1") (pinfunction "1_1") (pintype "passive"))
    )
    (net (code "53") (name "Net-(G5-PadA)") (class "Default")
      (node (ref "G5") (pin "A") (pinfunction "A_A") (pintype "passive"))
      (node (ref "R37") (pin "1") (pinfunction "1_1") (pintype "passive"))
    )
    (net (code "54") (name "Net-(G6-PadA)") (class "Default")
      (node (ref "G6") (pin "A") (pinfunction "A_A") (pintype "passive"))
      (node (ref "R38") (pin "1") (pinfunction "1_1") (pintype "passive"))
    )
    (net (code "55") (name "Net-(Q1-D)") (class "Default")
      (node (ref "Q1") (pin "3") (pinfunction "D_3") (pintype "bidirectional"))
      (node (ref "R45") (pin "1") (pinfunction "1_1") (pintype "passive"))
    )
    (net (code "56") (name "Net-(Q2-D)") (class "Default")
      (node (ref "Q2") (pin "3") (pinfunction "D_3") (pintype "bidirectional"))
      (node (ref "R1") (pin "2") (pinfunction "2_2") (pintype "passive"))
      (node (ref "R2") (pin "2") (pinfunction "2_2") (pintype "passive"))
      (node (ref "R3") (pin "2") (pinfunction "2_2") (pintype "passive"))
      (node (ref "R4") (pin "2") (pinfunction "2_2") (pintype "passive"))
      (node (ref "R5") (pin "2") (pinfunction "2_2") (pintype "passive"))
      (node (ref "R6") (pin "2") (pinfunction "2_2") (pintype "passive"))
    )
    (net (code "57") (name "Net-(Q2-G)") (class "Default")
      (node (ref "Q2") (pin "1") (pinfunction "G_1") (pintype "bidirectional"))
      (node (ref "R44") (pin "1") (pinfunction "1_1") (pintype "passive"))
      (node (ref "R45") (pin "2") (pinfunction "2_2") (pintype "passive"))
    )
    (net (code "58") (name "Net-(Q3-D)") (class "Default")
      (node (ref "JP2") (pin "2") (pinfunction "2_2") (pintype "passive"))
      (node (ref "Q3") (pin "3") (pinfunction "D_3") (pintype "bidirectional"))
      (node (ref "Q4") (pin "1") (pinfunction "G_1") (pintype "bidirectional"))
      (node (ref "R48") (pin "2") (pinfunction "2_2") (pintype "passive"))
    )
    (net (code "59") (name "Net-(Q3-G)") (class "Default")
      (node (ref "Q3") (pin "1") (pinfunction "G_1") (pintype "bidirectional"))
      (node (ref "R46") (pin "1") (pinfunction "1_1") (pintype "passive"))
      (node (ref "R47") (pin "1") (pinfunction "1_1") (pintype "passive"))
    )
    (net (code "60") (name "Net-(Q3-S)") (class "Default")
      (node (ref "JP1") (pin "1") (pinfunction "1_1") (pintype "passive"))
      (node (ref "Q3") (pin "2") (pinfunction "S_2") (pintype "bidirectional"))
      (node (ref "R47") (pin "2") (pinfunction "2_2") (pintype "passive"))
    )
    (net (code "61") (name "Net-(Q5-D)") (class "Default")
      (node (ref "Q5") (pin "3") (pinfunction "D_3") (pintype "bidirectional"))
      (node (ref "R10") (pin "2") (pinfunction "2_2") (pintype "passive"))
      (node (ref "R11") (pin "2") (pinfunction "2_2") (pintype "passive"))
      (node (ref "R7") (pin "2") (pinfunction "2_2") (pintype "passive"))
      (node (ref "R8") (pin "2") (pinfunction "2_2") (pintype "passive"))
      (node (ref "R9") (pin "2") (pinfunction "2_2") (pintype "passive"))
    )
    (net (code "62") (name "Net-(Q5-G)") (class "Default")
      (node (ref "Q5") (pin "1") (pinfunction "G_1") (pintype "bidirectional"))
      (node (ref "R49") (pin "1") (pinfunction "1_1") (pintype "passive"))
      (node (ref "R50") (pin "2") (pinfunction "2_2") (pintype "passive"))
    )
    (net (code "63") (name "Net-(Q6-D)") (class "Default")
      (node (ref "Q6") (pin "3") (pinfunction "D_3") (pintype "bidirectional"))
      (node (ref "R50") (pin "1") (pinfunction "1_1") (pintype "passive"))
    )
    (net (code "64") (name "Net-(Q7-D)") (class "Default")
      (node (ref "Q7") (pin "3") (pinfunction "D_3") (pintype "bidirectional"))
      (node (ref "R12") (pin "2") (pinfunction "2_2") (pintype "passive"))
      (node (ref "R13") (pin "2") (pinfunction "2_2") (pintype "passive"))
      (node (ref "R14") (pin "2") (pinfunction "2_2") (pintype "passive"))
      (node (ref "R15") (pin "2") (pinfunction "2_2") (pintype "passive"))
      (node (ref "R16") (pin "2") (pinfunction "2_2") (pintype "passive"))
    )
    (net (code "65") (name "Net-(Q7-G)") (class "Default")
      (node (ref "Q7") (pin "1") (pinfunction "G_1") (pintype "bidirectional"))
      (node (ref "R52") (pin "1") (pinfunction "1_1") (pintype "passive"))
      (node (ref "R53") (pin "2") (pinfunction "2_2") (pintype "passive"))
    )
    (net (code "66") (name "Net-(Q8-D)") (class "Default")
      (node (ref "Q8") (pin "3") (pinfunction "D_3") (pintype "bidirectional"))
      (node (ref "R53") (pin "1") (pinfunction "1_1") (pintype "passive"))
    )
    (net (code "67") (name "Net-(Q9-D)") (class "Default")
      (node (ref "Q9") (pin "3") (pinfunction "D_3") (pintype "bidirectional"))
      (node (ref "R17") (pin "2") (pinfunction "2_2") (pintype "passive"))
      (node (ref "R18") (pin "2") (pinfunction "2_2") (pintype "passive"))
      (node (ref "R19") (pin "2") (pinfunction "2_2") (pintype "passive"))
      (node (ref "R20") (pin "2") (pinfunction "2_2") (pintype "passive"))
      (node (ref "R21") (pin "2") (pinfunction "2_2") (pintype "passive"))
      (node (ref "R22") (pin "2") (pinfunction "2_2") (pintype "passive"))
    )
    (net (code "68") (name "Net-(Q9-G)") (class "Default")
      (node (ref "Q9") (pin "1") (pinfunction "G_1") (pintype "bidirectional"))
      (node (ref "R55") (pin "1") (pinfunction "1_1") (pintype "passive"))
      (node (ref "R56") (pin "2") (pinfunction "2_2") (pintype "passive"))
    )
    (net (code "69") (name "Net-(Q10-D)") (class "Default")
      (node (ref "Q10") (pin "3") (pinfunction "D_3") (pintype "bidirectional"))
      (node (ref "R56") (pin "1") (pinfunction "1_1") (pintype "passive"))
    )
    (net (code "70") (name "Net-(Q11-D)") (class "Default")
      (node (ref "Q11") (pin "3") (pinfunction "D_3") (pintype "bidirectional"))
      (node (ref "R23") (pin "2") (pinfunction "2_2") (pintype "passive"))
      (node (ref "R24") (pin "2") (pinfunction "2_2") (pintype "passive"))
      (node (ref "R25") (pin "2") (pinfunction "2_2") (pintype "passive"))
      (node (ref "R26") (pin "2") (pinfunction "2_2") (pintype "passive"))
      (node (ref "R27") (pin "2") (pinfunction "2_2") (pintype "passive"))
    )
    (net (code "71") (name "Net-(Q11-G)") (class "Default")
      (node (ref "Q11") (pin "1") (pinfunction "G_1") (pintype "bidirectional"))
      (node (ref "R58") (pin "1") (pinfunction "1_1") (pintype "passive"))
      (node (ref "R59") (pin "2") (pinfunction "2_2") (pintype "passive"))
    )
    (net (code "72") (name "Net-(Q12-D)") (class "Default")
      (node (ref "Q12") (pin "3") (pinfunction "D_3") (pintype "bidirectional"))
      (node (ref "R59") (pin "1") (pinfunction "1_1") (pintype "passive"))
    )
    (net (code "73") (name "Net-(Q13-D)") (class "Default")
      (node (ref "Q13") (pin "3") (pinfunction "D_3") (pintype "bidirectional"))
      (node (ref "R28") (pin "2") (pinfunction "2_2") (pintype "passive"))
      (node (ref "R29") (pin "2") (pinfunction "2_2") (pintype "passive"))
      (node (ref "R30") (pin "2") (pinfunction "2_2") (pintype "passive"))
      (node (ref "R31") (pin "2") (pinfunction "2_2") (pintype "passive"))
      (node (ref "R32") (pin "2") (pinfunction "2_2") (pintype "passive"))
    )
    (net (code "74") (name "Net-(Q13-G)") (class "Default")
      (node (ref "Q13") (pin "1") (pinfunction "G_1") (pintype "bidirectional"))
      (node (ref "R61") (pin "1") (pinfunction "1_1") (pintype "passive"))
      (node (ref "R62") (pin "2") (pinfunction "2_2") (pintype "passive"))
    )
    (net (code "75") (name "Net-(Q14-D)") (class "Default")
      (node (ref "Q14") (pin "3") (pinfunction "D_3") (pintype "bidirectional"))
      (node (ref "R62") (pin "1") (pinfunction "1_1") (pintype "passive"))
    )
    (net (code "76") (name "Net-(Q15-D)") (class "Default")
      (node (ref "Q15") (pin "3") (pinfunction "D_3") (pintype "bidirectional"))
      (node (ref "R33") (pin "2") (pinfunction "2_2") (pintype "passive"))
      (node (ref "R34") (pin "2") (pinfunction "2_2") (pintype "passive"))
      (node (ref "R35") (pin "2") (pinfunction "2_2") (pintype "passive"))
      (node (ref "R36") (pin "2") (pinfunction "2_2") (pintype "passive"))
      (node (ref "R37") (pin "2") (pinfunction "2_2") (pintype "passive"))
      (node (ref "R38") (pin "2") (pinfunction "2_2") (pintype "passive"))
    )
    (net (code "77") (name "Net-(Q15-G)") (class "Default")
      (node (ref "Q15") (pin "1") (pinfunction "G_1") (pintype "bidirectional"))
      (node (ref "R64") (pin "1") (pinfunction "1_1") (pintype "passive"))
      (node (ref "R65") (pin "2") (pinfunction "2_2") (pintype "passive"))
    )
    (net (code "78") (name "Net-(Q16-D)") (class "Default")
      (node (ref "Q16") (pin "3") (pinfunction "D_3") (pintype "bidirectional"))
      (node (ref "R65") (pin "1") (pinfunction "1_1") (pintype "passive"))
    )
    (net (code "79") (name "Net-(Q17-D)") (class "Default")
      (node (ref "Q17") (pin "3") (pinfunction "D_3") (pintype "bidirectional"))
      (node (ref "R39") (pin "2") (pinfunction "2_2") (pintype "passive"))
      (node (ref "R40") (pin "2") (pinfunction "2_2") (pintype "passive"))
      (node (ref "R41") (pin "2") (pinfunction "2_2") (pintype "passive"))
      (node (ref "R42") (pin "2") (pinfunction "2_2") (pintype "passive"))
    )
    (net (code "80") (name "Net-(Q17-G)") (class "Default")
      (node (ref "Q17") (pin "1") (pinfunction "G_1") (pintype "bidirectional"))
      (node (ref "R67") (pin "1") (pinfunction "1_1") (pintype "passive"))
      (node (ref "R68") (pin "2") (pinfunction "2_2") (pintype "passive"))
    )
    (net (code "81") (name "Net-(Q18-D)") (class "Default")
      (node (ref "Q18") (pin "3") (pinfunction "D_3") (pintype "bidirectional"))
      (node (ref "R68") (pin "1") (pinfunction "1_1") (pintype "passive"))
    )
    (net (code "82") (name "VCC") (class "Default")
      (node (ref "JP1") (pin "2") (pinfunction "2_2") (pintype "passive"))
      (node (ref "ON") (pin "3") (pinfunction "S_3") (pintype "passive"))
      (node (ref "Q11") (pin "2") (pinfunction "S_2") (pintype "bidirectional"))
      (node (ref "Q13") (pin "2") (pinfunction "S_2") (pintype "bidirectional"))
      (node (ref "Q15") (pin "2") (pinfunction "S_2") (pintype "bidirectional"))
      (node (ref "Q17") (pin "2") (pinfunction "S_2") (pintype "bidirectional"))
      (node (ref "Q2") (pin "2") (pinfunction "S_2") (pintype "bidirectional"))
      (node (ref "Q5") (pin "2") (pinfunction "S_2") (pintype "bidirectional"))
      (node (ref "Q7") (pin "2") (pinfunction "S_2") (pintype "bidirectional"))
      (node (ref "Q9") (pin "2") (pinfunction "S_2") (pintype "bidirectional"))
      (node (ref "R44") (pin "2") (pinfunction "2_2") (pintype "passive"))
      (node (ref "R49") (pin "2") (pinfunction "2_2") (pintype "passive"))
      (node (ref "R52") (pin "2") (pinfunction "2_2") (pintype "passive"))
      (node (ref "R55") (pin "2") (pinfunction "2_2") (pintype "passive"))
      (node (ref "R58") (pin "2") (pinfunction "2_2") (pintype "passive"))
      (node (ref "R61") (pin "2") (pinfunction "2_2") (pintype "passive"))
      (node (ref "R64") (pin "2") (pinfunction "2_2") (pintype "passive"))
      (node (ref "R67") (pin "2") (pinfunction "2_2") (pintype "passive"))
    )
  )
)
